# LC_LPF10.net
KiCad netlist of a schematic drawn in Altium Designer
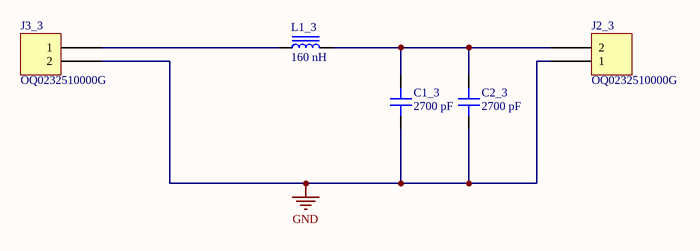
[diagram p0: LC_LPF10.SchDoc]

(export (version "E")
  (design (tool "Eeschema 10.0.6"))
  (components
    (comp (ref "C1_3")
      (value "2700 pF")
      (footprint "CAP 0603_1608")
      (description "CAP CER 2700PF 25V NP0 0603")
      (fields (field (name "PART NUMBER") "C0603C272F3GAC7867") (field (name "MANUFACTURER") "KEMET"))
      (libsource (lib "Celestial Altium Library - altium_library") (part "Capacitor"))
    )
    (comp (ref "C2_3")
      (value "2700 pF")
      (footprint "CAP 0603_1608")
      (description "CAP CER 2700PF 25V NP0 0603")
      (fields (field (name "PART NUMBER") "C0603C272F3GAC7867") (field (name "MANUFACTURER") "KEMET"))
      (libsource (lib "Celestial Altium Library - altium_library") (part "Capacitor"))
    )
    (comp (ref "J2_3")
      (value "OQ0232510000G")
      (footprint "FCI 06-381-2PIN")
      (description "TERM BLOCK HDR 2POS 90DEG 3.81MM")
      (fields (field (name "MANUFACTURER") "Amphenol Anytek"))
      (libsource (lib "Celestial Altium Library - altium_library") (part "2 Pin"))
    )
    (comp (ref "J3_3")
      (value "OQ0232510000G")
      (footprint "FCI 06-381-2PIN")
      (description "TERM BLOCK HDR 2POS 90DEG 3.81MM")
      (fields (field (name "MANUFACTURER") "Amphenol Anytek"))
      (libsource (lib "") (part "2 Pin_1"))
    )
    (comp (ref "L1_3")
      (value "160 nH")
      (footprint "IND 0402_1005 RF WW")
      (description "FIXED IND 160NH 480MA 330MOHM SM")
      (fields
        (field (name "PART NUMBER") "LQW15CNR16J00D")
        (field (name "MANUFACTURER") "Murata Electronics")
      )
      (libsource (lib "Celestial Altium Library - altium_library") (part "Inductor"))
    )
  )
  (nets
    (net (code "1") (name "GND") (class "Default")
      (node (ref "C1_3") (pin "1") (pinfunction "1_1") (pintype "passive"))
      (node (ref "C2_3") (pin "1") (pinfunction "1_1") (pintype "passive"))
      (node (ref "J2_3") (pin "1") (pinfunction "1_1") (pintype "passive"))
      (node (ref "J3_3") (pin "2") (pinfunction "2_2") (pintype "passive"))
    )
    (net (code "2") (name "Net-(C1_3-Pad2)") (class "Default")
      (node (ref "C1_3") (pin "2") (pinfunction "2_2") (pintype "passive"))
      (node (ref "C2_3") (pin "2") (pinfunction "2_2") (pintype "passive"))
      (node (ref "J2_3") (pin "2") (pinfunction "2_2") (pintype "passive"))
      (node (ref "L1_3") (pin "2") (pinfunction "2_2") (pintype "passive"))
    )
    (net (code "3") (name "Net-(J3_3-Pad1)") (class "Default")
      (node (ref "J3_3") (pin "1") (pinfunction "1_1") (pintype "passive"))
      (node (ref "L1_3") (pin "1") (pinfunction "1_1") (pintype "passive"))
    )
  )
)
